# Acc2BncBreakout.net
KiCad netlist of a schematic drawn in EAGLE
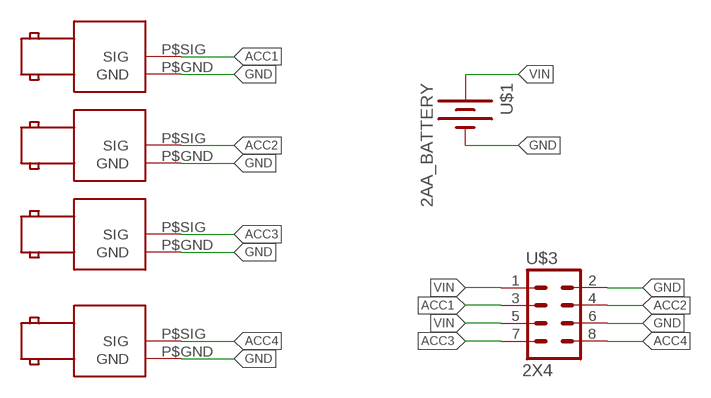
[diagram p0: schematic, sheet 1]

(export (version "E")
  (design (tool "Eeschema 10.0.6"))
  (components
    (comp (ref "ACC1")
      (value "BNC_RIGHT_ANGLE")
      (footprint "eagle-import:BNC_RIGHT_ANGLE")
      (libsource (lib "eagle-import") (part "BNC_RIGHT_ANGLE"))
    )
    (comp (ref "ACC2")
      (value "BNC_RIGHT_ANGLE")
      (footprint "eagle-import:BNC_RIGHT_ANGLE")
      (libsource (lib "eagle-import") (part "BNC_RIGHT_ANGLE"))
    )
    (comp (ref "ACC3")
      (value "BNC_RIGHT_ANGLE")
      (footprint "eagle-import:BNC_RIGHT_ANGLE")
      (libsource (lib "eagle-import") (part "BNC_RIGHT_ANGLE"))
    )
    (comp (ref "ACC4")
      (value "BNC_RIGHT_ANGLE")
      (footprint "eagle-import:BNC_RIGHT_ANGLE")
      (libsource (lib "eagle-import") (part "BNC_RIGHT_ANGLE"))
    )
    (comp (ref "U$1")
      (value "2AA_BATTERY")
      (footprint "eagle-import:2AA_PLASTIC_HOLDER")
      (libsource (lib "eagle-import") (part "2AA_BATTERY"))
    )
    (comp (ref "U$3")
      (value "2X4")
      (footprint "eagle-import:2X4_SHROUDED_BERG")
      (libsource (lib "eagle-import") (part "2X4"))
    )
  )
  (nets
    (net (code "1") (name "ACC1") (class "Default")
      (node (ref "ACC1") (pin "P$SIG") (pinfunction "SIG_P$SIG") (pintype "bidirectional"))
      (node (ref "U$3") (pin "3") (pinfunction "3_3") (pintype "passive"))
    )
    (net (code "2") (name "ACC2") (class "Default")
      (node (ref "ACC2") (pin "P$SIG") (pinfunction "SIG_P$SIG") (pintype "bidirectional"))
      (node (ref "U$3") (pin "4") (pinfunction "4_4") (pintype "passive"))
    )
    (net (code "3") (name "ACC3") (class "Default")
      (node (ref "ACC3") (pin "P$SIG") (pinfunction "SIG_P$SIG") (pintype "bidirectional"))
      (node (ref "U$3") (pin "7") (pinfunction "7_7") (pintype "passive"))
    )
    (net (code "4") (name "ACC4") (class "Default")
      (node (ref "ACC4") (pin "P$SIG") (pinfunction "SIG_P$SIG") (pintype "bidirectional"))
      (node (ref "U$3") (pin "8") (pinfunction "8_8") (pintype "passive"))
    )
    (net (code "5") (name "GND") (class "Default")
      (node (ref "ACC1") (pin "P$GND") (pinfunction "GND_P$GND") (pintype "bidirectional"))
      (node (ref "ACC2") (pin "P$GND") (pinfunction "GND_P$GND") (pintype "bidirectional"))
      (node (ref "ACC3") (pin "P$GND") (pinfunction "GND_P$GND") (pintype "bidirectional"))
      (node (ref "ACC4") (pin "P$GND") (pinfunction "GND_P$GND") (pintype "bidirectional"))
      (node (ref "U$1") (pin "PWR@4") (pinfunction "-_PWR@4") (pintype "power_in"))
      (node (ref "U$3") (pin "2") (pinfunction "2_2") (pintype "passive"))
      (node (ref "U$3") (pin "6") (pinfunction "6_6") (pintype "passive"))
    )
    (net (code "6") (name "VIN") (class "Default")
      (node (ref "U$1") (pin "PWR@3") (pinfunction "+_PWR@3") (pintype "power_in"))
      (node (ref "U$3") (pin "1") (pinfunction "1_1") (pintype "passive"))
      (node (ref "U$3") (pin "5") (pinfunction "5_5") (pintype "passive"))
    )
  )
)
